# main_pcb.net
KiCad netlist of a schematic drawn in EAGLE
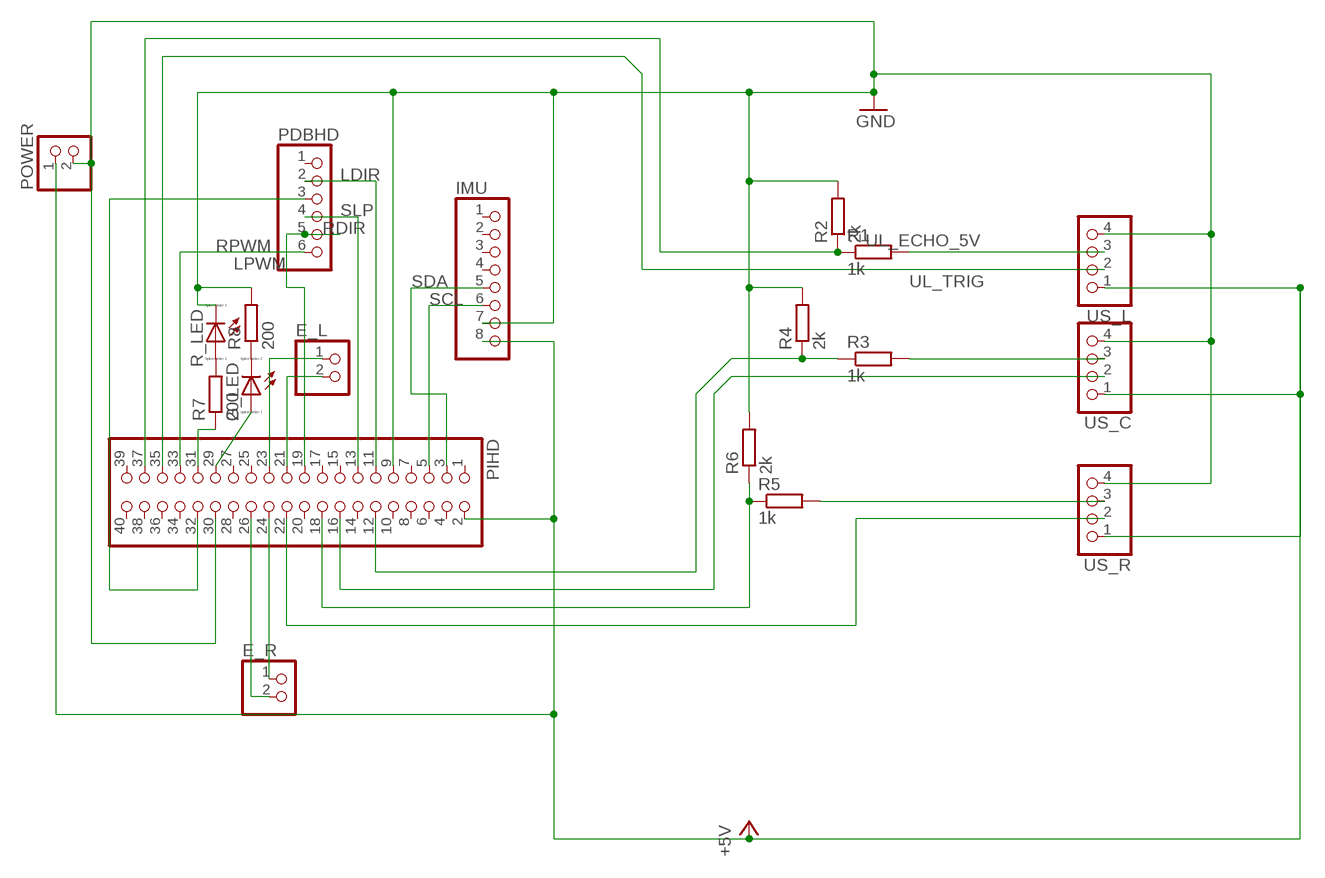
[diagram p0: schematic, sheet 1]

(export (version "E")
  (design (tool "Eeschema 10.0.6"))
  (components
    (comp (ref "E_L")
      (value "PINHD-1X2")
      (footprint "eagle-import:1X02")
      (libsource (lib "eagle-import") (part "PINHD-1X2"))
    )
    (comp (ref "E_R")
      (value "PINHD-1X2")
      (footprint "eagle-import:1X02")
      (libsource (lib "eagle-import") (part "PINHD-1X2"))
    )
    (comp (ref "G_LED")
      (value "LED_ELD260")
      (footprint "eagle-import:LED_LD260")
      (libsource (lib "eagle-import") (part "LED_ELD260"))
    )
    (comp (ref "IMU")
      (value "PINHD-1X8")
      (footprint "eagle-import:1X08")
      (libsource (lib "eagle-import") (part "PINHD-1X8"))
    )
    (comp (ref "PDBHD")
      (value "PINHD-1X6")
      (footprint "eagle-import:1X06")
      (libsource (lib "eagle-import") (part "PINHD-1X6"))
    )
    (comp (ref "PIHD")
      (value "PINHD-2X20")
      (footprint "eagle-import:2X20")
      (libsource (lib "eagle-import") (part "PINHD-2X20"))
    )
    (comp (ref "POWER")
      (value "PINHD-1X2")
      (footprint "eagle-import:1X02")
      (libsource (lib "eagle-import") (part "PINHD-1X2"))
    )
    (comp (ref "R1")
      (value "1k")
      (footprint "eagle-import:0207_10")
      (libsource (lib "eagle-import") (part "R-EU_0207/10"))
    )
    (comp (ref "R2")
      (value "2k")
      (footprint "eagle-import:0207_10")
      (libsource (lib "eagle-import") (part "R-EU_0207/10"))
    )
    (comp (ref "R3")
      (value "1k")
      (footprint "eagle-import:0207_10")
      (libsource (lib "eagle-import") (part "R-EU_0207/10"))
    )
    (comp (ref "R4")
      (value "2k")
      (footprint "eagle-import:0207_10")
      (libsource (lib "eagle-import") (part "R-EU_0207/10"))
    )
    (comp (ref "R5")
      (value "1k")
      (footprint "eagle-import:0207_10")
      (libsource (lib "eagle-import") (part "R-EU_0207/10"))
    )
    (comp (ref "R6")
      (value "2k")
      (footprint "eagle-import:0207_10")
      (libsource (lib "eagle-import") (part "R-EU_0207/10"))
    )
    (comp (ref "R7")
      (value "200")
      (footprint "eagle-import:0207_10")
      (libsource (lib "eagle-import") (part "R-EU_0207/10"))
    )
    (comp (ref "R8")
      (value "200")
      (footprint "eagle-import:0207_10")
      (libsource (lib "eagle-import") (part "R-EU_0207/10"))
    )
    (comp (ref "R_LED")
      (value "LED_ELD260")
      (footprint "eagle-import:LED_LD260")
      (libsource (lib "eagle-import") (part "LED_ELD260"))
    )
    (comp (ref "US_C")
      (value "PINHD-1X4")
      (footprint "eagle-import:1X04")
      (libsource (lib "eagle-import") (part "PINHD-1X4"))
    )
    (comp (ref "US_L")
      (value "PINHD-1X4")
      (footprint "eagle-import:1X04")
      (libsource (lib "eagle-import") (part "PINHD-1X4"))
    )
    (comp (ref "US_R")
      (value "PINHD-1X4")
      (footprint "eagle-import:1X04")
      (libsource (lib "eagle-import") (part "PINHD-1X4"))
    )
  )
  (nets
    (net (code "1") (name "+5V") (class "Default")
      (node (ref "IMU") (pin "8") (pinfunction "8_8") (pintype "passive"))
      (node (ref "PIHD") (pin "2") (pinfunction "2_2") (pintype "passive"))
      (node (ref "POWER") (pin "1") (pinfunction "1_1") (pintype "passive"))
      (node (ref "US_C") (pin "1") (pinfunction "1_1") (pintype "passive"))
      (node (ref "US_L") (pin "1") (pinfunction "1_1") (pintype "passive"))
      (node (ref "US_R") (pin "1") (pinfunction "1_1") (pintype "passive"))
    )
    (net (code "2") (name "/LDIR") (class "Default")
      (node (ref "PDBHD") (pin "2") (pinfunction "2_2") (pintype "passive"))
      (node (ref "PIHD") (pin "11") (pinfunction "11_11") (pintype "passive"))
    )
    (net (code "3") (name "/LPWM") (class "Default")
      (node (ref "PDBHD") (pin "3") (pinfunction "3_3") (pintype "passive"))
      (node (ref "PIHD") (pin "32") (pinfunction "32_32") (pintype "passive"))
    )
    (net (code "4") (name "/RDIR") (class "Default")
      (node (ref "PDBHD") (pin "5") (pinfunction "5_5") (pintype "passive"))
      (node (ref "PIHD") (pin "19") (pinfunction "19_19") (pintype "passive"))
    )
    (net (code "5") (name "/RPWM") (class "Default")
      (node (ref "PDBHD") (pin "6") (pinfunction "6_6") (pintype "passive"))
      (node (ref "PIHD") (pin "33") (pinfunction "33_33") (pintype "passive"))
    )
    (net (code "6") (name "/SCL") (class "Default")
      (node (ref "IMU") (pin "6") (pinfunction "6_6") (pintype "passive"))
      (node (ref "PIHD") (pin "5") (pinfunction "5_5") (pintype "passive"))
    )
    (net (code "7") (name "/SDA") (class "Default")
      (node (ref "IMU") (pin "5") (pinfunction "5_5") (pintype "passive"))
      (node (ref "PIHD") (pin "3") (pinfunction "3_3") (pintype "passive"))
    )
    (net (code "8") (name "/SLP") (class "Default")
      (node (ref "PDBHD") (pin "4") (pinfunction "4_4") (pintype "passive"))
      (node (ref "PIHD") (pin "13") (pinfunction "13_13") (pintype "passive"))
    )
    (net (code "9") (name "/UL_ECHO_5V") (class "Default")
      (node (ref "R1") (pin "2") (pinfunction "2_2") (pintype "passive"))
      (node (ref "US_L") (pin "3") (pinfunction "3_3") (pintype "passive"))
    )
    (net (code "10") (name "/UL_TRIG") (class "Default")
      (node (ref "PIHD") (pin "35") (pinfunction "35_35") (pintype "passive"))
      (node (ref "US_L") (pin "2") (pinfunction "2_2") (pintype "passive"))
    )
    (net (code "11") (name "GND") (class "Default")
      (node (ref "IMU") (pin "7") (pinfunction "7_7") (pintype "passive"))
      (node (ref "PIHD") (pin "30") (pinfunction "30_30") (pintype "passive"))
      (node (ref "PIHD") (pin "9") (pinfunction "9_9") (pintype "passive"))
      (node (ref "POWER") (pin "2") (pinfunction "2_2") (pintype "passive"))
      (node (ref "R2") (pin "2") (pinfunction "2_2") (pintype "passive"))
      (node (ref "R4") (pin "2") (pinfunction "2_2") (pintype "passive"))
      (node (ref "R6") (pin "2") (pinfunction "2_2") (pintype "passive"))
      (node (ref "R8") (pin "2") (pinfunction "2_2") (pintype "passive"))
      (node (ref "R_LED") (pin "K") (pinfunction "C_K") (pintype "passive"))
      (node (ref "US_C") (pin "4") (pinfunction "4_4") (pintype "passive"))
      (node (ref "US_L") (pin "4") (pinfunction "4_4") (pintype "passive"))
      (node (ref "US_R") (pin "4") (pinfunction "4_4") (pintype "passive"))
    )
    (net (code "12") (name "Net-(E_L-Pad1)") (class "Default")
      (node (ref "E_L") (pin "1") (pinfunction "1_1") (pintype "passive"))
      (node (ref "PIHD") (pin "23") (pinfunction "23_23") (pintype "passive"))
    )
    (net (code "13") (name "Net-(E_L-Pad2)") (class "Default")
      (node (ref "E_L") (pin "2") (pinfunction "2_2") (pintype "passive"))
      (node (ref "PIHD") (pin "21") (pinfunction "21_21") (pintype "passive"))
    )
    (net (code "14") (name "Net-(E_R-Pad1)") (class "Default")
      (node (ref "E_R") (pin "1") (pinfunction "1_1") (pintype "passive"))
      (node (ref "PIHD") (pin "24") (pinfunction "24_24") (pintype "passive"))
    )
    (net (code "15") (name "Net-(E_R-Pad2)") (class "Default")
      (node (ref "E_R") (pin "2") (pinfunction "2_2") (pintype "passive"))
      (node (ref "PIHD") (pin "26") (pinfunction "26_26") (pintype "passive"))
    )
    (net (code "16") (name "Net-(G_LED-C)") (class "Default")
      (node (ref "G_LED") (pin "K") (pinfunction "C_K") (pintype "passive"))
      (node (ref "R8") (pin "1") (pinfunction "1_1") (pintype "passive"))
    )
    (net (code "17") (name "Net-(G_LED-PadA)") (class "Default")
      (node (ref "G_LED") (pin "A") (pinfunction "A_A") (pintype "passive"))
      (node (ref "PIHD") (pin "29") (pinfunction "29_29") (pintype "passive"))
    )
    (net (code "18") (name "Net-(PIHD-Pad12)") (class "Default")
      (node (ref "PIHD") (pin "12") (pinfunction "12_12") (pintype "passive"))
      (node (ref "R3") (pin "1") (pinfunction "1_1") (pintype "passive"))
      (node (ref "R4") (pin "1") (pinfunction "1_1") (pintype "passive"))
    )
    (net (code "19") (name "Net-(PIHD-Pad16)") (class "Default")
      (node (ref "PIHD") (pin "16") (pinfunction "16_16") (pintype "passive"))
      (node (ref "US_C") (pin "2") (pinfunction "2_2") (pintype "passive"))
    )
    (net (code "20") (name "Net-(PIHD-Pad18)") (class "Default")
      (node (ref "PIHD") (pin "18") (pinfunction "18_18") (pintype "passive"))
      (node (ref "R5") (pin "1") (pinfunction "1_1") (pintype "passive"))
      (node (ref "R6") (pin "1") (pinfunction "1_1") (pintype "passive"))
    )
    (net (code "21") (name "Net-(PIHD-Pad22)") (class "Default")
      (node (ref "PIHD") (pin "22") (pinfunction "22_22") (pintype "passive"))
      (node (ref "US_R") (pin "2") (pinfunction "2_2") (pintype "passive"))
    )
    (net (code "22") (name "Net-(PIHD-Pad31)") (class "Default")
      (node (ref "PIHD") (pin "31") (pinfunction "31_31") (pintype "passive"))
      (node (ref "R7") (pin "1") (pinfunction "1_1") (pintype "passive"))
    )
    (net (code "23") (name "Net-(PIHD-Pad37)") (class "Default")
      (node (ref "PIHD") (pin "37") (pinfunction "37_37") (pintype "passive"))
      (node (ref "R1") (pin "1") (pinfunction "1_1") (pintype "passive"))
      (node (ref "R2") (pin "1") (pinfunction "1_1") (pintype "passive"))
    )
    (net (code "24") (name "Net-(R3-Pad2)") (class "Default")
      (node (ref "R3") (pin "2") (pinfunction "2_2") (pintype "passive"))
      (node (ref "US_C") (pin "3") (pinfunction "3_3") (pintype "passive"))
    )
    (net (code "25") (name "Net-(R5-Pad2)") (class "Default")
      (node (ref "R5") (pin "2") (pinfunction "2_2") (pintype "passive"))
      (node (ref "US_R") (pin "3") (pinfunction "3_3") (pintype "passive"))
    )
    (net (code "26") (name "Net-(R7-Pad2)") (class "Default")
      (node (ref "R7") (pin "2") (pinfunction "2_2") (pintype "passive"))
      (node (ref "R_LED") (pin "A") (pinfunction "A_A") (pintype "passive"))
    )
    (net (code "27") (name "unconnected-(IMU-Pad1)") (class "Default")
      (node (ref "IMU") (pin "1") (pinfunction "1_1") (pintype "passive"))
    )
    (net (code "28") (name "unconnected-(IMU-Pad2)") (class "Default")
      (node (ref "IMU") (pin "2") (pinfunction "2_2") (pintype "passive"))
    )
    (net (code "29") (name "unconnected-(IMU-Pad3)") (class "Default")
      (node (ref "IMU") (pin "3") (pinfunction "3_3") (pintype "passive"))
    )
    (net (code "30") (name "unconnected-(IMU-Pad4)") (class "Default")
      (node (ref "IMU") (pin "4") (pinfunction "4_4") (pintype "passive"))
    )
    (net (code "31") (name "unconnected-(PDBHD-Pad1)") (class "Default")
      (node (ref "PDBHD") (pin "1") (pinfunction "1_1") (pintype "passive"))
    )
    (net (code "32") (name "unconnected-(PIHD-Pad1)") (class "Default")
      (node (ref "PIHD") (pin "1") (pinfunction "1_1") (pintype "passive"))
    )
    (net (code "33") (name "unconnected-(PIHD-Pad4)") (class "Default")
      (node (ref "PIHD") (pin "4") (pinfunction "4_4") (pintype "passive"))
    )
    (net (code "34") (name "unconnected-(PIHD-Pad6)") (class "Default")
      (node (ref "PIHD") (pin "6") (pinfunction "6_6") (pintype "passive"))
    )
    (net (code "35") (name "unconnected-(PIHD-Pad7)") (class "Default")
      (node (ref "PIHD") (pin "7") (pinfunction "7_7") (pintype "passive"))
    )
    (net (code "36") (name "unconnected-(PIHD-Pad8)") (class "Default")
      (node (ref "PIHD") (pin "8") (pinfunction "8_8") (pintype "passive"))
    )
    (net (code "37") (name "unconnected-(PIHD-Pad10)") (class "Default")
      (node (ref "PIHD") (pin "10") (pinfunction "10_10") (pintype "passive"))
    )
    (net (code "38") (name "unconnected-(PIHD-Pad14)") (class "Default")
      (node (ref "PIHD") (pin "14") (pinfunction "14_14") (pintype "passive"))
    )
    (net (code "39") (name "unconnected-(PIHD-Pad15)") (class "Default")
      (node (ref "PIHD") (pin "15") (pinfunction "15_15") (pintype "passive"))
    )
    (net (code "40") (name "unconnected-(PIHD-Pad17)") (class "Default")
      (node (ref "PIHD") (pin "17") (pinfunction "17_17") (pintype "passive"))
    )
    (net (code "41") (name "unconnected-(PIHD-Pad20)") (class "Default")
      (node (ref "PIHD") (pin "20") (pinfunction "20_20") (pintype "passive"))
    )
    (net (code "42") (name "unconnected-(PIHD-Pad25)") (class "Default")
      (node (ref "PIHD") (pin "25") (pinfunction "25_25") (pintype "passive"))
    )
    (net (code "43") (name "unconnected-(PIHD-Pad27)") (class "Default")
      (node (ref "PIHD") (pin "27") (pinfunction "27_27") (pintype "passive"))
    )
    (net (code "44") (name "unconnected-(PIHD-Pad28)") (class "Default")
      (node (ref "PIHD") (pin "28") (pinfunction "28_28") (pintype "passive"))
    )
    (net (code "45") (name "unconnected-(PIHD-Pad34)") (class "Default")
      (node (ref "PIHD") (pin "34") (pinfunction "34_34") (pintype "passive"))
    )
    (net (code "46") (name "unconnected-(PIHD-Pad36)") (class "Default")
      (node (ref "PIHD") (pin "36") (pinfunction "36_36") (pintype "passive"))
    )
    (net (code "47") (name "unconnected-(PIHD-Pad38)") (class "Default")
      (node (ref "PIHD") (pin "38") (pinfunction "38_38") (pintype "passive"))
    )
    (net (code "48") (name "unconnected-(PIHD-Pad39)") (class "Default")
      (node (ref "PIHD") (pin "39") (pinfunction "39_39") (pintype "passive"))
    )
    (net (code "49") (name "unconnected-(PIHD-Pad40)") (class "Default")
      (node (ref "PIHD") (pin "40") (pinfunction "40_40") (pintype "passive"))
    )
  )
)
